# DE-270624.net
KiCad netlist of a schematic drawn in Altium Designer
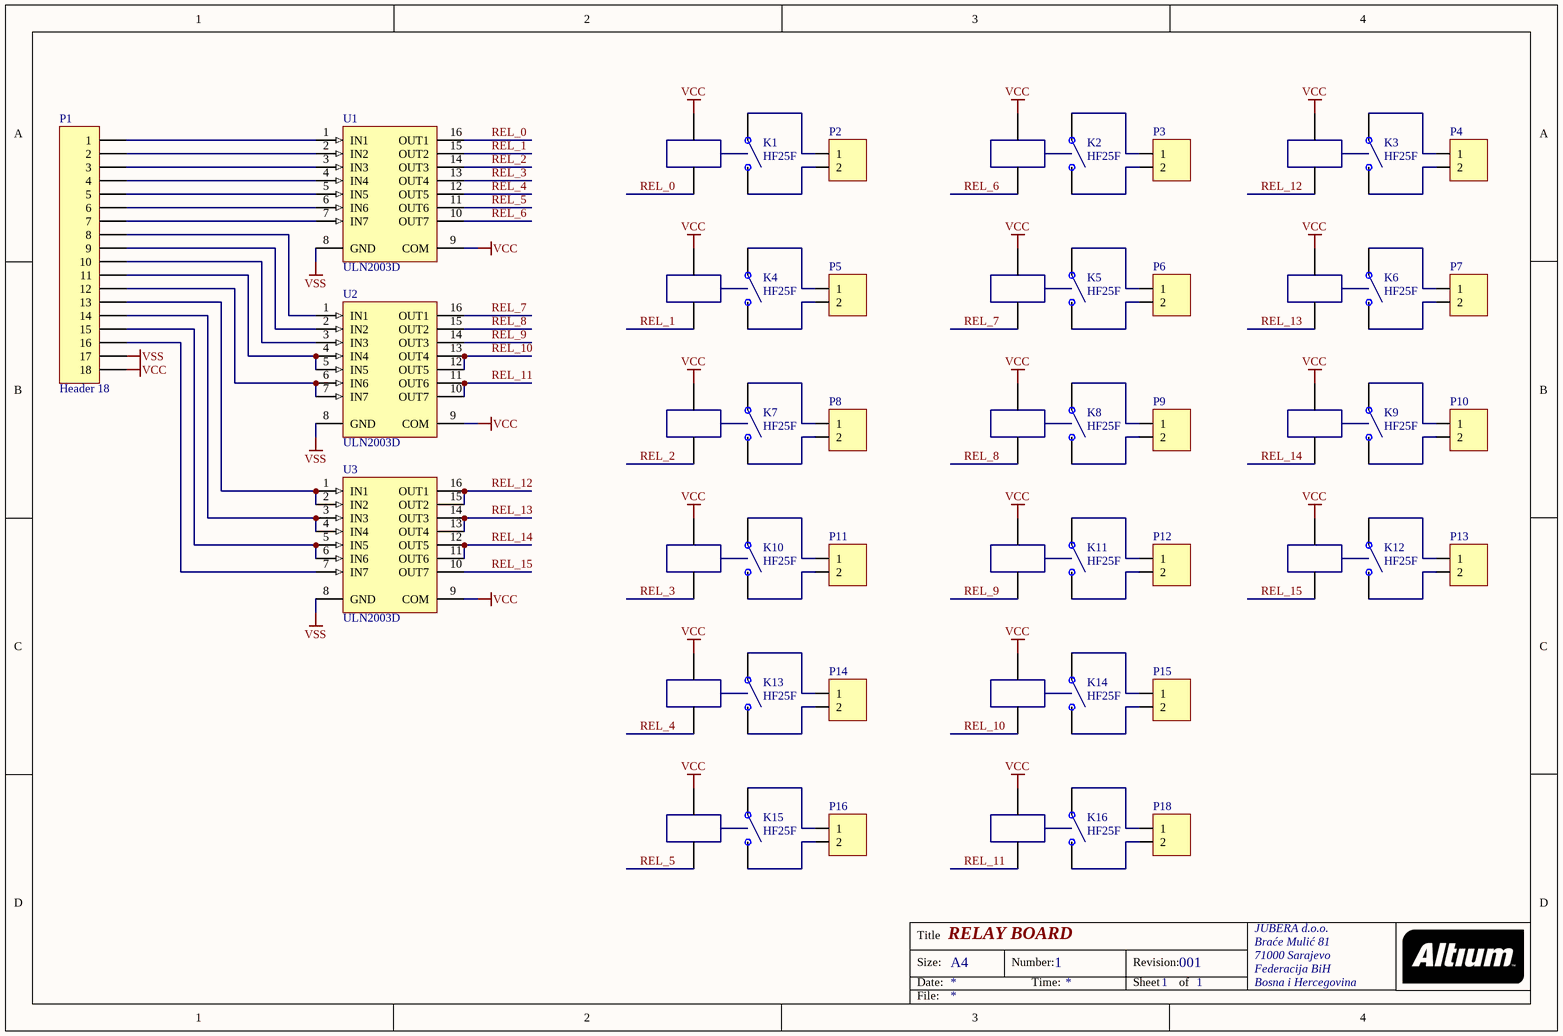
[diagram p0: DE-270624.SchDoc]

(export (version "E")
  (design (tool "Eeschema 10.0.6"))
  (components
    (comp (ref "K1")
      (value "HF25F")
      (footprint "HF25F")
      (description "PCB relay 250VAC/20A 30VDC/16A")
      (libsource (lib "DE-270624") (part "HF25F"))
    )
    (comp (ref "K2")
      (value "HF25F")
      (footprint "HF25F")
      (description "PCB relay 250VAC/20A 30VDC/16A")
      (libsource (lib "DE-270624") (part "HF25F"))
    )
    (comp (ref "K3")
      (value "HF25F")
      (footprint "HF25F")
      (description "PCB relay 250VAC/20A 30VDC/16A")
      (libsource (lib "DE-270624") (part "HF25F"))
    )
    (comp (ref "K4")
      (value "HF25F")
      (footprint "HF25F")
      (description "PCB relay 250VAC/20A 30VDC/16A")
      (libsource (lib "DE-270624") (part "HF25F"))
    )
    (comp (ref "K5")
      (value "HF25F")
      (footprint "HF25F")
      (description "PCB relay 250VAC/20A 30VDC/16A")
      (libsource (lib "DE-270624") (part "HF25F"))
    )
    (comp (ref "K6")
      (value "HF25F")
      (footprint "HF25F")
      (description "PCB relay 250VAC/20A 30VDC/16A")
      (libsource (lib "DE-270624") (part "HF25F"))
    )
    (comp (ref "K7")
      (value "HF25F")
      (footprint "HF25F")
      (description "PCB relay 250VAC/20A 30VDC/16A")
      (libsource (lib "DE-270624") (part "HF25F"))
    )
    (comp (ref "K8")
      (value "HF25F")
      (footprint "HF25F")
      (description "PCB relay 250VAC/20A 30VDC/16A")
      (libsource (lib "DE-270624") (part "HF25F"))
    )
    (comp (ref "K9")
      (value "HF25F")
      (footprint "HF25F")
      (description "PCB relay 250VAC/20A 30VDC/16A")
      (libsource (lib "DE-270624") (part "HF25F"))
    )
    (comp (ref "K10")
      (value "HF25F")
      (footprint "HF25F")
      (description "PCB relay 250VAC/20A 30VDC/16A")
      (libsource (lib "DE-270624") (part "HF25F"))
    )
    (comp (ref "K11")
      (value "HF25F")
      (footprint "HF25F")
      (description "PCB relay 250VAC/20A 30VDC/16A")
      (libsource (lib "DE-270624") (part "HF25F"))
    )
    (comp (ref "K12")
      (value "HF25F")
      (footprint "HF25F")
      (description "PCB relay 250VAC/20A 30VDC/16A")
      (libsource (lib "DE-270624") (part "HF25F"))
    )
    (comp (ref "K13")
      (value "HF25F")
      (footprint "HF25F")
      (description "PCB relay 250VAC/20A 30VDC/16A")
      (libsource (lib "DE-270624") (part "HF25F"))
    )
    (comp (ref "K14")
      (value "HF25F")
      (footprint "HF25F")
      (description "PCB relay 250VAC/20A 30VDC/16A")
      (libsource (lib "DE-270624") (part "HF25F"))
    )
    (comp (ref "K15")
      (value "HF25F")
      (footprint "HF25F")
      (description "PCB relay 250VAC/20A 30VDC/16A")
      (libsource (lib "DE-270624") (part "HF25F"))
    )
    (comp (ref "K16")
      (value "HF25F")
      (footprint "HF25F")
      (description "PCB relay 250VAC/20A 30VDC/16A")
      (libsource (lib "DE-270624") (part "HF25F"))
    )
    (comp (ref "P1")
      (value "Header 18")
      (footprint "HDR1X18")
      (description "Header, 18-Pin")
      (fields (field (name "PUBLISHER") "Altium Limited"))
      (libsource (lib "Miscellaneous Connectors") (part "Header 18"))
    )
    (comp (ref "P2")
      (value "220Vac")
      (footprint "TERMINAL BLOK 2 - 3,5mm")
      (description "Terminal blok konektor 3,5 mm")
      (libsource (lib "DE-270624") (part "TERMINAL BLOK 2"))
    )
    (comp (ref "P3")
      (value "220Vac")
      (footprint "TERMINAL BLOK 2 - 3,5mm")
      (description "Terminal blok konektor 3,5 mm")
      (libsource (lib "DE-270624") (part "TERMINAL BLOK 2"))
    )
    (comp (ref "P4")
      (value "220Vac")
      (footprint "TERMINAL BLOK 2 - 3,5mm")
      (description "Terminal blok konektor 3,5 mm")
      (libsource (lib "DE-270624") (part "TERMINAL BLOK 2"))
    )
    (comp (ref "P5")
      (value "220Vac")
      (footprint "TERMINAL BLOK 2 - 3,5mm")
      (description "Terminal blok konektor 3,5 mm")
      (libsource (lib "DE-270624") (part "TERMINAL BLOK 2"))
    )
    (comp (ref "P6")
      (value "220Vac")
      (footprint "TERMINAL BLOK 2 - 3,5mm")
      (description "Terminal blok konektor 3,5 mm")
      (libsource (lib "DE-270624") (part "TERMINAL BLOK 2"))
    )
    (comp (ref "P7")
      (value "220Vac")
      (footprint "TERMINAL BLOK 2 - 3,5mm")
      (description "Terminal blok konektor 3,5 mm")
      (libsource (lib "DE-270624") (part "TERMINAL BLOK 2"))
    )
    (comp (ref "P8")
      (value "220Vac")
      (footprint "TERMINAL BLOK 2 - 3,5mm")
      (description "Terminal blok konektor 3,5 mm")
      (libsource (lib "DE-270624") (part "TERMINAL BLOK 2"))
    )
    (comp (ref "P9")
      (value "220Vac")
      (footprint "TERMINAL BLOK 2 - 3,5mm")
      (description "Terminal blok konektor 3,5 mm")
      (libsource (lib "DE-270624") (part "TERMINAL BLOK 2"))
    )
    (comp (ref "P10")
      (value "220Vac")
      (footprint "TERMINAL BLOK 2 - 3,5mm")
      (description "Terminal blok konektor 3,5 mm")
      (libsource (lib "DE-270624") (part "TERMINAL BLOK 2"))
    )
    (comp (ref "P11")
      (value "220Vac")
      (footprint "TERMINAL BLOK 2 - 3,5mm")
      (description "Terminal blok konektor 3,5 mm")
      (libsource (lib "DE-270624") (part "TERMINAL BLOK 2"))
    )
    (comp (ref "P12")
      (value "220Vac")
      (footprint "TERMINAL BLOK 2 - 3,5mm")
      (description "Terminal blok konektor 3,5 mm")
      (libsource (lib "DE-270624") (part "TERMINAL BLOK 2"))
    )
    (comp (ref "P13")
      (value "220Vac")
      (footprint "TERMINAL BLOK 2 - 3,5mm")
      (description "Terminal blok konektor 3,5 mm")
      (libsource (lib "DE-270624") (part "TERMINAL BLOK 2"))
    )
    (comp (ref "P14")
      (value "220Vac")
      (footprint "TERMINAL BLOK 2 - 3,5mm")
      (description "Terminal blok konektor 3,5 mm")
      (libsource (lib "DE-270624") (part "TERMINAL BLOK 2"))
    )
    (comp (ref "P15")
      (value "220Vac")
      (footprint "TERMINAL BLOK 2 - 3,5mm")
      (description "Terminal blok konektor 3,5 mm")
      (libsource (lib "DE-270624") (part "TERMINAL BLOK 2"))
    )
    (comp (ref "P16")
      (value "220Vac")
      (footprint "TERMINAL BLOK 2 - 3,5mm")
      (description "Terminal blok konektor 3,5 mm")
      (libsource (lib "DE-270624") (part "TERMINAL BLOK 2"))
    )
    (comp (ref "P18")
      (value "220Vac")
      (footprint "TERMINAL BLOK 2 - 3,5mm")
      (description "Terminal blok konektor 3,5 mm")
      (libsource (lib "DE-270624") (part "TERMINAL BLOK 2"))
    )
    (comp (ref "U1")
      (value "ULN2003D")
      (footprint "SO16_N")
      (description "Seven Darlington Array")
      (fields (field (name "PUBLISHER") "Altium Limited"))
      (libsource (lib "DE-270124") (part "ULN2003D"))
    )
    (comp (ref "U2")
      (value "ULN2003D")
      (footprint "SO16_N")
      (description "Seven Darlington Array")
      (fields (field (name "PUBLISHER") "Altium Limited"))
      (libsource (lib "DE-270124") (part "ULN2003D"))
    )
    (comp (ref "U3")
      (value "ULN2003D")
      (footprint "SO16_N")
      (description "Seven Darlington Array")
      (fields (field (name "PUBLISHER") "Altium Limited"))
      (libsource (lib "DE-270124") (part "ULN2003D"))
    )
  )
  (nets
    (net (code "1") (name "/REL_0") (class "Default")
      (node (ref "K1") (pin "2") (pinfunction "2_2") (pintype "passive"))
      (node (ref "U1") (pin "16") (pinfunction "OUT1_16") (pintype "open_collector"))
    )
    (net (code "2") (name "/REL_1") (class "Default")
      (node (ref "K4") (pin "2") (pinfunction "2_2") (pintype "passive"))
      (node (ref "U1") (pin "15") (pinfunction "OUT2_15") (pintype "open_collector"))
    )
    (net (code "3") (name "/REL_2") (class "Default")
      (node (ref "K7") (pin "2") (pinfunction "2_2") (pintype "passive"))
      (node (ref "U1") (pin "14") (pinfunction "OUT3_14") (pintype "open_collector"))
    )
    (net (code "4") (name "/REL_3") (class "Default")
      (node (ref "K10") (pin "2") (pinfunction "2_2") (pintype "passive"))
      (node (ref "U1") (pin "13") (pinfunction "OUT4_13") (pintype "open_collector"))
    )
    (net (code "5") (name "/REL_4") (class "Default")
      (node (ref "K13") (pin "2") (pinfunction "2_2") (pintype "passive"))
      (node (ref "U1") (pin "12") (pinfunction "OUT5_12") (pintype "open_collector"))
    )
    (net (code "6") (name "/REL_5") (class "Default")
      (node (ref "K15") (pin "2") (pinfunction "2_2") (pintype "passive"))
      (node (ref "U1") (pin "11") (pinfunction "OUT6_11") (pintype "open_collector"))
    )
    (net (code "7") (name "/REL_6") (class "Default")
      (node (ref "K2") (pin "2") (pinfunction "2_2") (pintype "passive"))
      (node (ref "U1") (pin "10") (pinfunction "OUT7_10") (pintype "open_collector"))
    )
    (net (code "8") (name "/REL_7") (class "Default")
      (node (ref "K5") (pin "2") (pinfunction "2_2") (pintype "passive"))
      (node (ref "U2") (pin "16") (pinfunction "OUT1_16") (pintype "open_collector"))
    )
    (net (code "9") (name "/REL_8") (class "Default")
      (node (ref "K8") (pin "2") (pinfunction "2_2") (pintype "passive"))
      (node (ref "U2") (pin "15") (pinfunction "OUT2_15") (pintype "open_collector"))
    )
    (net (code "10") (name "/REL_9") (class "Default")
      (node (ref "K11") (pin "2") (pinfunction "2_2") (pintype "passive"))
      (node (ref "U2") (pin "14") (pinfunction "OUT3_14") (pintype "open_collector"))
    )
    (net (code "11") (name "/REL_10") (class "Default")
      (node (ref "K14") (pin "2") (pinfunction "2_2") (pintype "passive"))
      (node (ref "U2") (pin "12") (pinfunction "OUT5_12") (pintype "open_collector"))
      (node (ref "U2") (pin "13") (pinfunction "OUT4_13") (pintype "open_collector"))
    )
    (net (code "12") (name "/REL_11") (class "Default")
      (node (ref "K16") (pin "2") (pinfunction "2_2") (pintype "passive"))
      (node (ref "U2") (pin "10") (pinfunction "OUT7_10") (pintype "open_collector"))
      (node (ref "U2") (pin "11") (pinfunction "OUT6_11") (pintype "open_collector"))
    )
    (net (code "13") (name "/REL_12") (class "Default")
      (node (ref "K3") (pin "2") (pinfunction "2_2") (pintype "passive"))
      (node (ref "U3") (pin "15") (pinfunction "OUT2_15") (pintype "open_collector"))
      (node (ref "U3") (pin "16") (pinfunction "OUT1_16") (pintype "open_collector"))
    )
    (net (code "14") (name "/REL_13") (class "Default")
      (node (ref "K6") (pin "2") (pinfunction "2_2") (pintype "passive"))
      (node (ref "U3") (pin "13") (pinfunction "OUT4_13") (pintype "open_collector"))
      (node (ref "U3") (pin "14") (pinfunction "OUT3_14") (pintype "open_collector"))
    )
    (net (code "15") (name "/REL_14") (class "Default")
      (node (ref "K9") (pin "2") (pinfunction "2_2") (pintype "passive"))
      (node (ref "U3") (pin "11") (pinfunction "OUT6_11") (pintype "open_collector"))
      (node (ref "U3") (pin "12") (pinfunction "OUT5_12") (pintype "open_collector"))
    )
    (net (code "16") (name "/REL_15") (class "Default")
      (node (ref "K12") (pin "2") (pinfunction "2_2") (pintype "passive"))
      (node (ref "U3") (pin "10") (pinfunction "OUT7_10") (pintype "open_collector"))
    )
    (net (code "17") (name "Net-(K1-Pad3)") (class "Default")
      (node (ref "K1") (pin "3") (pinfunction "3_3") (pintype "passive"))
      (node (ref "P2") (pin "1") (pinfunction "1_1") (pintype "passive"))
    )
    (net (code "18") (name "Net-(K1-Pad4)") (class "Default")
      (node (ref "K1") (pin "4") (pinfunction "4_4") (pintype "passive"))
      (node (ref "P2") (pin "2") (pinfunction "2_2") (pintype "passive"))
    )
    (net (code "19") (name "Net-(K2-Pad3)") (class "Default")
      (node (ref "K2") (pin "3") (pinfunction "3_3") (pintype "passive"))
      (node (ref "P3") (pin "1") (pinfunction "1_1") (pintype "passive"))
    )
    (net (code "20") (name "Net-(K2-Pad4)") (class "Default")
      (node (ref "K2") (pin "4") (pinfunction "4_4") (pintype "passive"))
      (node (ref "P3") (pin "2") (pinfunction "2_2") (pintype "passive"))
    )
    (net (code "21") (name "Net-(K3-Pad3)") (class "Default")
      (node (ref "K3") (pin "3") (pinfunction "3_3") (pintype "passive"))
      (node (ref "P4") (pin "1") (pinfunction "1_1") (pintype "passive"))
    )
    (net (code "22") (name "Net-(K3-Pad4)") (class "Default")
      (node (ref "K3") (pin "4") (pinfunction "4_4") (pintype "passive"))
      (node (ref "P4") (pin "2") (pinfunction "2_2") (pintype "passive"))
    )
    (net (code "23") (name "Net-(K4-Pad3)") (class "Default")
      (node (ref "K4") (pin "3") (pinfunction "3_3") (pintype "passive"))
      (node (ref "P5") (pin "1") (pinfunction "1_1") (pintype "passive"))
    )
    (net (code "24") (name "Net-(K4-Pad4)") (class "Default")
      (node (ref "K4") (pin "4") (pinfunction "4_4") (pintype "passive"))
      (node (ref "P5") (pin "2") (pinfunction "2_2") (pintype "passive"))
    )
    (net (code "25") (name "Net-(K5-Pad3)") (class "Default")
      (node (ref "K5") (pin "3") (pinfunction "3_3") (pintype "passive"))
      (node (ref "P6") (pin "1") (pinfunction "1_1") (pintype "passive"))
    )
    (net (code "26") (name "Net-(K5-Pad4)") (class "Default")
      (node (ref "K5") (pin "4") (pinfunction "4_4") (pintype "passive"))
      (node (ref "P6") (pin "2") (pinfunction "2_2") (pintype "passive"))
    )
    (net (code "27") (name "Net-(K6-Pad3)") (class "Default")
      (node (ref "K6") (pin "3") (pinfunction "3_3") (pintype "passive"))
      (node (ref "P7") (pin "1") (pinfunction "1_1") (pintype "passive"))
    )
    (net (code "28") (name "Net-(K6-Pad4)") (class "Default")
      (node (ref "K6") (pin "4") (pinfunction "4_4") (pintype "passive"))
      (node (ref "P7") (pin "2") (pinfunction "2_2") (pintype "passive"))
    )
    (net (code "29") (name "Net-(K7-Pad3)") (class "Default")
      (node (ref "K7") (pin "3") (pinfunction "3_3") (pintype "passive"))
      (node (ref "P8") (pin "1") (pinfunction "1_1") (pintype "passive"))
    )
    (net (code "30") (name "Net-(K7-Pad4)") (class "Default")
      (node (ref "K7") (pin "4") (pinfunction "4_4") (pintype "passive"))
      (node (ref "P8") (pin "2") (pinfunction "2_2") (pintype "passive"))
    )
    (net (code "31") (name "Net-(K8-Pad3)") (class "Default")
      (node (ref "K8") (pin "3") (pinfunction "3_3") (pintype "passive"))
      (node (ref "P9") (pin "1") (pinfunction "1_1") (pintype "passive"))
    )
    (net (code "32") (name "Net-(K8-Pad4)") (class "Default")
      (node (ref "K8") (pin "4") (pinfunction "4_4") (pintype "passive"))
      (node (ref "P9") (pin "2") (pinfunction "2_2") (pintype "passive"))
    )
    (net (code "33") (name "Net-(K9-Pad3)") (class "Default")
      (node (ref "K9") (pin "3") (pinfunction "3_3") (pintype "passive"))
      (node (ref "P10") (pin "1") (pinfunction "1_1") (pintype "passive"))
    )
    (net (code "34") (name "Net-(K9-Pad4)") (class "Default")
      (node (ref "K9") (pin "4") (pinfunction "4_4") (pintype "passive"))
      (node (ref "P10") (pin "2") (pinfunction "2_2") (pintype "passive"))
    )
    (net (code "35") (name "Net-(K10-Pad3)") (class "Default")
      (node (ref "K10") (pin "3") (pinfunction "3_3") (pintype "passive"))
      (node (ref "P11") (pin "1") (pinfunction "1_1") (pintype "passive"))
    )
    (net (code "36") (name "Net-(K10-Pad4)") (class "Default")
      (node (ref "K10") (pin "4") (pinfunction "4_4") (pintype "passive"))
      (node (ref "P11") (pin "2") (pinfunction "2_2") (pintype "passive"))
    )
    (net (code "37") (name "Net-(K11-Pad3)") (class "Default")
      (node (ref "K11") (pin "3") (pinfunction "3_3") (pintype "passive"))
      (node (ref "P12") (pin "1") (pinfunction "1_1") (pintype "passive"))
    )
    (net (code "38") (name "Net-(K11-Pad4)") (class "Default")
      (node (ref "K11") (pin "4") (pinfunction "4_4") (pintype "passive"))
      (node (ref "P12") (pin "2") (pinfunction "2_2") (pintype "passive"))
    )
    (net (code "39") (name "Net-(K12-Pad3)") (class "Default")
      (node (ref "K12") (pin "3") (pinfunction "3_3") (pintype "passive"))
      (node (ref "P13") (pin "1") (pinfunction "1_1") (pintype "passive"))
    )
    (net (code "40") (name "Net-(K12-Pad4)") (class "Default")
      (node (ref "K12") (pin "4") (pinfunction "4_4") (pintype "passive"))
      (node (ref "P13") (pin "2") (pinfunction "2_2") (pintype "passive"))
    )
    (net (code "41") (name "Net-(K13-Pad3)") (class "Default")
      (node (ref "K13") (pin "3") (pinfunction "3_3") (pintype "passive"))
      (node (ref "P14") (pin "1") (pinfunction "1_1") (pintype "passive"))
    )
    (net (code "42") (name "Net-(K13-Pad4)") (class "Default")
      (node (ref "K13") (pin "4") (pinfunction "4_4") (pintype "passive"))
      (node (ref "P14") (pin "2") (pinfunction "2_2") (pintype "passive"))
    )
    (net (code "43") (name "Net-(K14-Pad3)") (class "Default")
      (node (ref "K14") (pin "3") (pinfunction "3_3") (pintype "passive"))
      (node (ref "P15") (pin "1") (pinfunction "1_1") (pintype "passive"))
    )
    (net (code "44") (name "Net-(K14-Pad4)") (class "Default")
      (node (ref "K14") (pin "4") (pinfunction "4_4") (pintype "passive"))
      (node (ref "P15") (pin "2") (pinfunction "2_2") (pintype "passive"))
    )
    (net (code "45") (name "Net-(K15-Pad3)") (class "Default")
      (node (ref "K15") (pin "3") (pinfunction "3_3") (pintype "passive"))
      (node (ref "P16") (pin "1") (pinfunction "1_1") (pintype "passive"))
    )
    (net (code "46") (name "Net-(K15-Pad4)") (class "Default")
      (node (ref "K15") (pin "4") (pinfunction "4_4") (pintype "passive"))
      (node (ref "P16") (pin "2") (pinfunction "2_2") (pintype "passive"))
    )
    (net (code "47") (name "Net-(K16-Pad3)") (class "Default")
      (node (ref "K16") (pin "3") (pinfunction "3_3") (pintype "passive"))
      (node (ref "P18") (pin "1") (pinfunction "1_1") (pintype "passive"))
    )
    (net (code "48") (name "Net-(K16-Pad4)") (class "Default")
      (node (ref "K16") (pin "4") (pinfunction "4_4") (pintype "passive"))
      (node (ref "P18") (pin "2") (pinfunction "2_2") (pintype "passive"))
    )
    (net (code "49") (name "Net-(U1-IN1)") (class "Default")
      (node (ref "P1") (pin "1") (pinfunction "1_1") (pintype "passive"))
      (node (ref "U1") (pin "1") (pinfunction "IN1_1") (pintype "input"))
    )
    (net (code "50") (name "Net-(U1-IN2)") (class "Default")
      (node (ref "P1") (pin "2") (pinfunction "2_2") (pintype "passive"))
      (node (ref "U1") (pin "2") (pinfunction "IN2_2") (pintype "input"))
    )
    (net (code "51") (name "Net-(U1-IN3)") (class "Default")
      (node (ref "P1") (pin "3") (pinfunction "3_3") (pintype "passive"))
      (node (ref "U1") (pin "3") (pinfunction "IN3_3") (pintype "input"))
    )
    (net (code "52") (name "Net-(U1-IN4)") (class "Default")
      (node (ref "P1") (pin "4") (pinfunction "4_4") (pintype "passive"))
      (node (ref "U1") (pin "4") (pinfunction "IN4_4") (pintype "input"))
    )
    (net (code "53") (name "Net-(U1-IN5)") (class "Default")
      (node (ref "P1") (pin "5") (pinfunction "5_5") (pintype "passive"))
      (node (ref "U1") (pin "5") (pinfunction "IN5_5") (pintype "input"))
    )
    (net (code "54") (name "Net-(U1-IN6)") (class "Default")
      (node (ref "P1") (pin "6") (pinfunction "6_6") (pintype "passive"))
      (node (ref "U1") (pin "6") (pinfunction "IN6_6") (pintype "input"))
    )
    (net (code "55") (name "Net-(U1-IN7)") (class "Default")
      (node (ref "P1") (pin "7") (pinfunction "7_7") (pintype "passive"))
      (node (ref "U1") (pin "7") (pinfunction "IN7_7") (pintype "input"))
    )
    (net (code "56") (name "Net-(U2-IN1)") (class "Default")
      (node (ref "P1") (pin "8") (pinfunction "8_8") (pintype "passive"))
      (node (ref "U2") (pin "1") (pinfunction "IN1_1") (pintype "input"))
    )
    (net (code "57") (name "Net-(U2-IN2)") (class "Default")
      (node (ref "P1") (pin "9") (pinfunction "9_9") (pintype "passive"))
      (node (ref "U2") (pin "2") (pinfunction "IN2_2") (pintype "input"))
    )
    (net (code "58") (name "Net-(U2-IN3)") (class "Default")
      (node (ref "P1") (pin "10") (pinfunction "10_10") (pintype "passive"))
      (node (ref "U2") (pin "3") (pinfunction "IN3_3") (pintype "input"))
    )
    (net (code "59") (name "Net-(U2-IN4)") (class "Default")
      (node (ref "P1") (pin "11") (pinfunction "11_11") (pintype "passive"))
      (node (ref "U2") (pin "4") (pinfunction "IN4_4") (pintype "input"))
      (node (ref "U2") (pin "5") (pinfunction "IN5_5") (pintype "input"))
    )
    (net (code "60") (name "Net-(U2-IN6)") (class "Default")
      (node (ref "P1") (pin "12") (pinfunction "12_12") (pintype "passive"))
      (node (ref "U2") (pin "6") (pinfunction "IN6_6") (pintype "input"))
      (node (ref "U2") (pin "7") (pinfunction "IN7_7") (pintype "input"))
    )
    (net (code "61") (name "Net-(U3-IN1)") (class "Default")
      (node (ref "P1") (pin "13") (pinfunction "13_13") (pintype "passive"))
      (node (ref "U3") (pin "1") (pinfunction "IN1_1") (pintype "input"))
      (node (ref "U3") (pin "2") (pinfunction "IN2_2") (pintype "input"))
    )
    (net (code "62") (name "Net-(U3-IN3)") (class "Default")
      (node (ref "P1") (pin "14") (pinfunction "14_14") (pintype "passive"))
      (node (ref "U3") (pin "3") (pinfunction "IN3_3") (pintype "input"))
      (node (ref "U3") (pin "4") (pinfunction "IN4_4") (pintype "input"))
    )
    (net (code "63") (name "Net-(U3-IN5)") (class "Default")
      (node (ref "P1") (pin "15") (pinfunction "15_15") (pintype "passive"))
      (node (ref "U3") (pin "5") (pinfunction "IN5_5") (pintype "input"))
      (node (ref "U3") (pin "6") (pinfunction "IN6_6") (pintype "input"))
    )
    (net (code "64") (name "Net-(U3-IN7)") (class "Default")
      (node (ref "P1") (pin "16") (pinfunction "16_16") (pintype "passive"))
      (node (ref "U3") (pin "7") (pinfunction "IN7_7") (pintype "input"))
    )
    (net (code "65") (name "VCC") (class "Default")
      (node (ref "K1") (pin "1") (pinfunction "1_1") (pintype "passive"))
      (node (ref "K10") (pin "1") (pinfunction "1_1") (pintype "passive"))
      (node (ref "K11") (pin "1") (pinfunction "1_1") (pintype "passive"))
      (node (ref "K12") (pin "1") (pinfunction "1_1") (pintype "passive"))
      (node (ref "K13") (pin "1") (pinfunction "1_1") (pintype "passive"))
      (node (ref "K14") (pin "1") (pinfunction "1_1") (pintype "passive"))
      (node (ref "K15") (pin "1") (pinfunction "1_1") (pintype "passive"))
      (node (ref "K16") (pin "1") (pinfunction "1_1") (pintype "passive"))
      (node (ref "K2") (pin "1") (pinfunction "1_1") (pintype "passive"))
      (node (ref "K3") (pin "1") (pinfunction "1_1") (pintype "passive"))
      (node (ref "K4") (pin "1") (pinfunction "1_1") (pintype "passive"))
      (node (ref "K5") (pin "1") (pinfunction "1_1") (pintype "passive"))
      (node (ref "K6") (pin "1") (pinfunction "1_1") (pintype "passive"))
      (node (ref "K7") (pin "1") (pinfunction "1_1") (pintype "passive"))
      (node (ref "K8") (pin "1") (pinfunction "1_1") (pintype "passive"))
      (node (ref "K9") (pin "1") (pinfunction "1_1") (pintype "passive"))
      (node (ref "P1") (pin "18") (pinfunction "18_18") (pintype "passive"))
      (node (ref "U1") (pin "9") (pinfunction "COM_9") (pintype "passive"))
      (node (ref "U2") (pin "9") (pinfunction "COM_9") (pintype "passive"))
      (node (ref "U3") (pin "9") (pinfunction "COM_9") (pintype "passive"))
    )
    (net (code "66") (name "VSS") (class "Default")
      (node (ref "P1") (pin "17") (pinfunction "17_17") (pintype "passive"))
      (node (ref "U1") (pin "8") (pinfunction "GND_8") (pintype "power_in"))
      (node (ref "U2") (pin "8") (pinfunction "GND_8") (pintype "power_in"))
      (node (ref "U3") (pin "8") (pinfunction "GND_8") (pintype "power_in"))
    )
  )
)
